# MostekH.net
KiCad netlist of a schematic drawn in Altium Designer
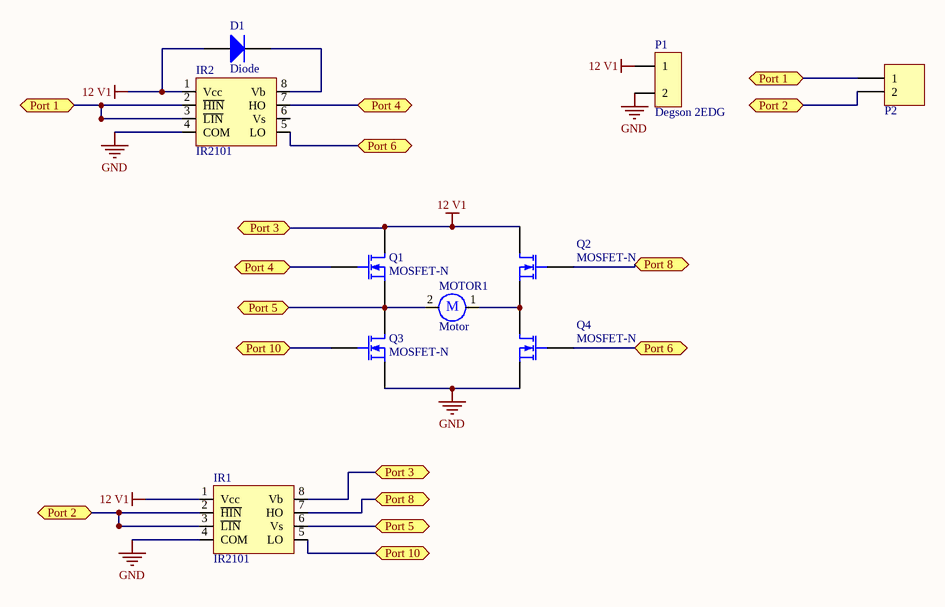
[diagram p0: MostekH.SchDoc]

(export (version "E")
  (design (tool "Eeschema 10.0.6"))
  (components
    (comp (ref "D1")
      (value "Diode")
      (footprint "SMC")
      (description "Default Diode")
      (fields (field (name "PUBLISHER") "Altium Limited"))
      (libsource (lib "Miscellaneous Devices") (part "Diode"))
    )
    (comp (ref "IR1")
      (value "IR2101")
      (footprint "PCBComponent_1")
      (libsource (lib "my_lib_microchips") (part "IR2101"))
    )
    (comp (ref "IR2")
      (value "IR2101")
      (footprint "PCBComponent_1")
      (libsource (lib "my_lib_microchips") (part "IR2101"))
    )
    (comp (ref "MOTOR1")
      (value "Motor")
      (footprint "HDR1X2")
      (description "Motor, General Kind")
      (fields (field (name "PUBLISHER") "Altium Limited"))
      (libsource (lib "KNR_Kurs") (part "Motor"))
    )
    (comp (ref "P1")
      (value "Degson 2EDG")
      (footprint "2EDGRC")
      (libsource (lib "KNR_Kurs") (part "Degson 2EDG"))
    )
    (comp (ref "P2")
      (value "HDR1X2")
      (footprint "HDR1X2")
      (description "Header, 2-Pin")
      (fields (field (name "PUBLISHER") "Altium Limited"))
      (libsource (lib "KNR_Kurs") (part "HDR1X2"))
    )
    (comp (ref "Q1")
      (value "MOSFET-N")
      (footprint "E3")
      (description "N-Channel MOSFET")
      (fields (field (name "PUBLISHER") "Altium Limited"))
      (libsource (lib "Miscellaneous Devices") (part "MOSFET-N"))
    )
    (comp (ref "Q2")
      (value "MOSFET-N")
      (footprint "E3")
      (description "N-Channel MOSFET")
      (fields (field (name "PUBLISHER") "Altium Limited"))
      (libsource (lib "Miscellaneous Devices") (part "MOSFET-N"))
    )
    (comp (ref "Q3")
      (value "MOSFET-N")
      (footprint "E3")
      (description "N-Channel MOSFET")
      (fields (field (name "PUBLISHER") "Altium Limited"))
      (libsource (lib "Miscellaneous Devices") (part "MOSFET-N"))
    )
    (comp (ref "Q4")
      (value "MOSFET-N")
      (footprint "E3")
      (description "N-Channel MOSFET")
      (fields (field (name "PUBLISHER") "Altium Limited"))
      (libsource (lib "Miscellaneous Devices") (part "MOSFET-N"))
    )
  )
  (nets
    (net (code "1") (name "/Port 1") (class "Default")
      (node (ref "IR2") (pin "2") (pinfunction "~{HIN}_2") (pintype "passive"))
      (node (ref "IR2") (pin "3") (pinfunction "~{LIN}_3") (pintype "passive"))
      (node (ref "P2") (pin "1") (pinfunction "1_1") (pintype "passive"))
    )
    (net (code "2") (name "/Port 2") (class "Default")
      (node (ref "IR1") (pin "2") (pinfunction "~{HIN}_2") (pintype "passive"))
      (node (ref "IR1") (pin "3") (pinfunction "~{LIN}_3") (pintype "passive"))
      (node (ref "P2") (pin "2") (pinfunction "2_2") (pintype "passive"))
    )
    (net (code "3") (name "/Port 4") (class "Default")
      (node (ref "IR2") (pin "7") (pinfunction "HO_7") (pintype "passive"))
      (node (ref "Q1") (pin "2") (pinfunction "G_2") (pintype "passive"))
    )
    (net (code "4") (name "/Port 5") (class "Default")
      (node (ref "IR1") (pin "6") (pinfunction "Vs_6") (pintype "passive"))
      (node (ref "MOTOR1") (pin "2") (pinfunction "2_2") (pintype "passive"))
      (node (ref "Q1") (pin "3") (pinfunction "S_3") (pintype "passive"))
      (node (ref "Q3") (pin "1") (pinfunction "D_1") (pintype "passive"))
    )
    (net (code "5") (name "/Port 6") (class "Default")
      (node (ref "IR2") (pin "5") (pinfunction "LO_5") (pintype "passive"))
      (node (ref "Q4") (pin "2") (pinfunction "G_2") (pintype "passive"))
    )
    (net (code "6") (name "/Port 8") (class "Default")
      (node (ref "IR1") (pin "7") (pinfunction "HO_7") (pintype "passive"))
      (node (ref "Q2") (pin "2") (pinfunction "G_2") (pintype "passive"))
    )
    (net (code "7") (name "/Port 10") (class "Default")
      (node (ref "IR1") (pin "5") (pinfunction "LO_5") (pintype "passive"))
      (node (ref "Q3") (pin "2") (pinfunction "G_2") (pintype "passive"))
    )
    (net (code "8") (name "12 V1") (class "Default")
      (node (ref "D1") (pin "1") (pinfunction "A_1") (pintype "passive"))
      (node (ref "IR1") (pin "1") (pinfunction "Vcc_1") (pintype "passive"))
      (node (ref "IR1") (pin "8") (pinfunction "Vb_8") (pintype "passive"))
      (node (ref "IR2") (pin "1") (pinfunction "Vcc_1") (pintype "passive"))
      (node (ref "P1") (pin "1") (pinfunction "1_1") (pintype "passive"))
      (node (ref "Q1") (pin "1") (pinfunction "D_1") (pintype "passive"))
      (node (ref "Q2") (pin "1") (pinfunction "D_1") (pintype "passive"))
    )
    (net (code "9") (name "GND") (class "Default")
      (node (ref "IR1") (pin "4") (pinfunction "COM_4") (pintype "passive"))
      (node (ref "IR2") (pin "4") (pinfunction "COM_4") (pintype "passive"))
      (node (ref "P1") (pin "2") (pinfunction "2_2") (pintype "passive"))
      (node (ref "Q3") (pin "3") (pinfunction "S_3") (pintype "passive"))
      (node (ref "Q4") (pin "3") (pinfunction "S_3") (pintype "passive"))
    )
    (net (code "10") (name "Net-(D1-K)") (class "Default")
      (node (ref "D1") (pin "2") (pinfunction "K_2") (pintype "passive"))
      (node (ref "IR2") (pin "8") (pinfunction "Vb_8") (pintype "passive"))
    )
    (net (code "11") (name "Net-(Q2-S)") (class "Default")
      (node (ref "MOTOR1") (pin "1") (pinfunction "1_1") (pintype "passive"))
      (node (ref "Q2") (pin "3") (pinfunction "S_3") (pintype "passive"))
      (node (ref "Q4") (pin "1") (pinfunction "D_1") (pintype "passive"))
    )
    (net (code "12") (name "unconnected-(IR2-Vs-Pad6)") (class "Default")
      (node (ref "IR2") (pin "6") (pinfunction "Vs_6") (pintype "passive"))
    )
  )
)
